# untitled.net
KiCad netlist of a schematic drawn in EAGLE
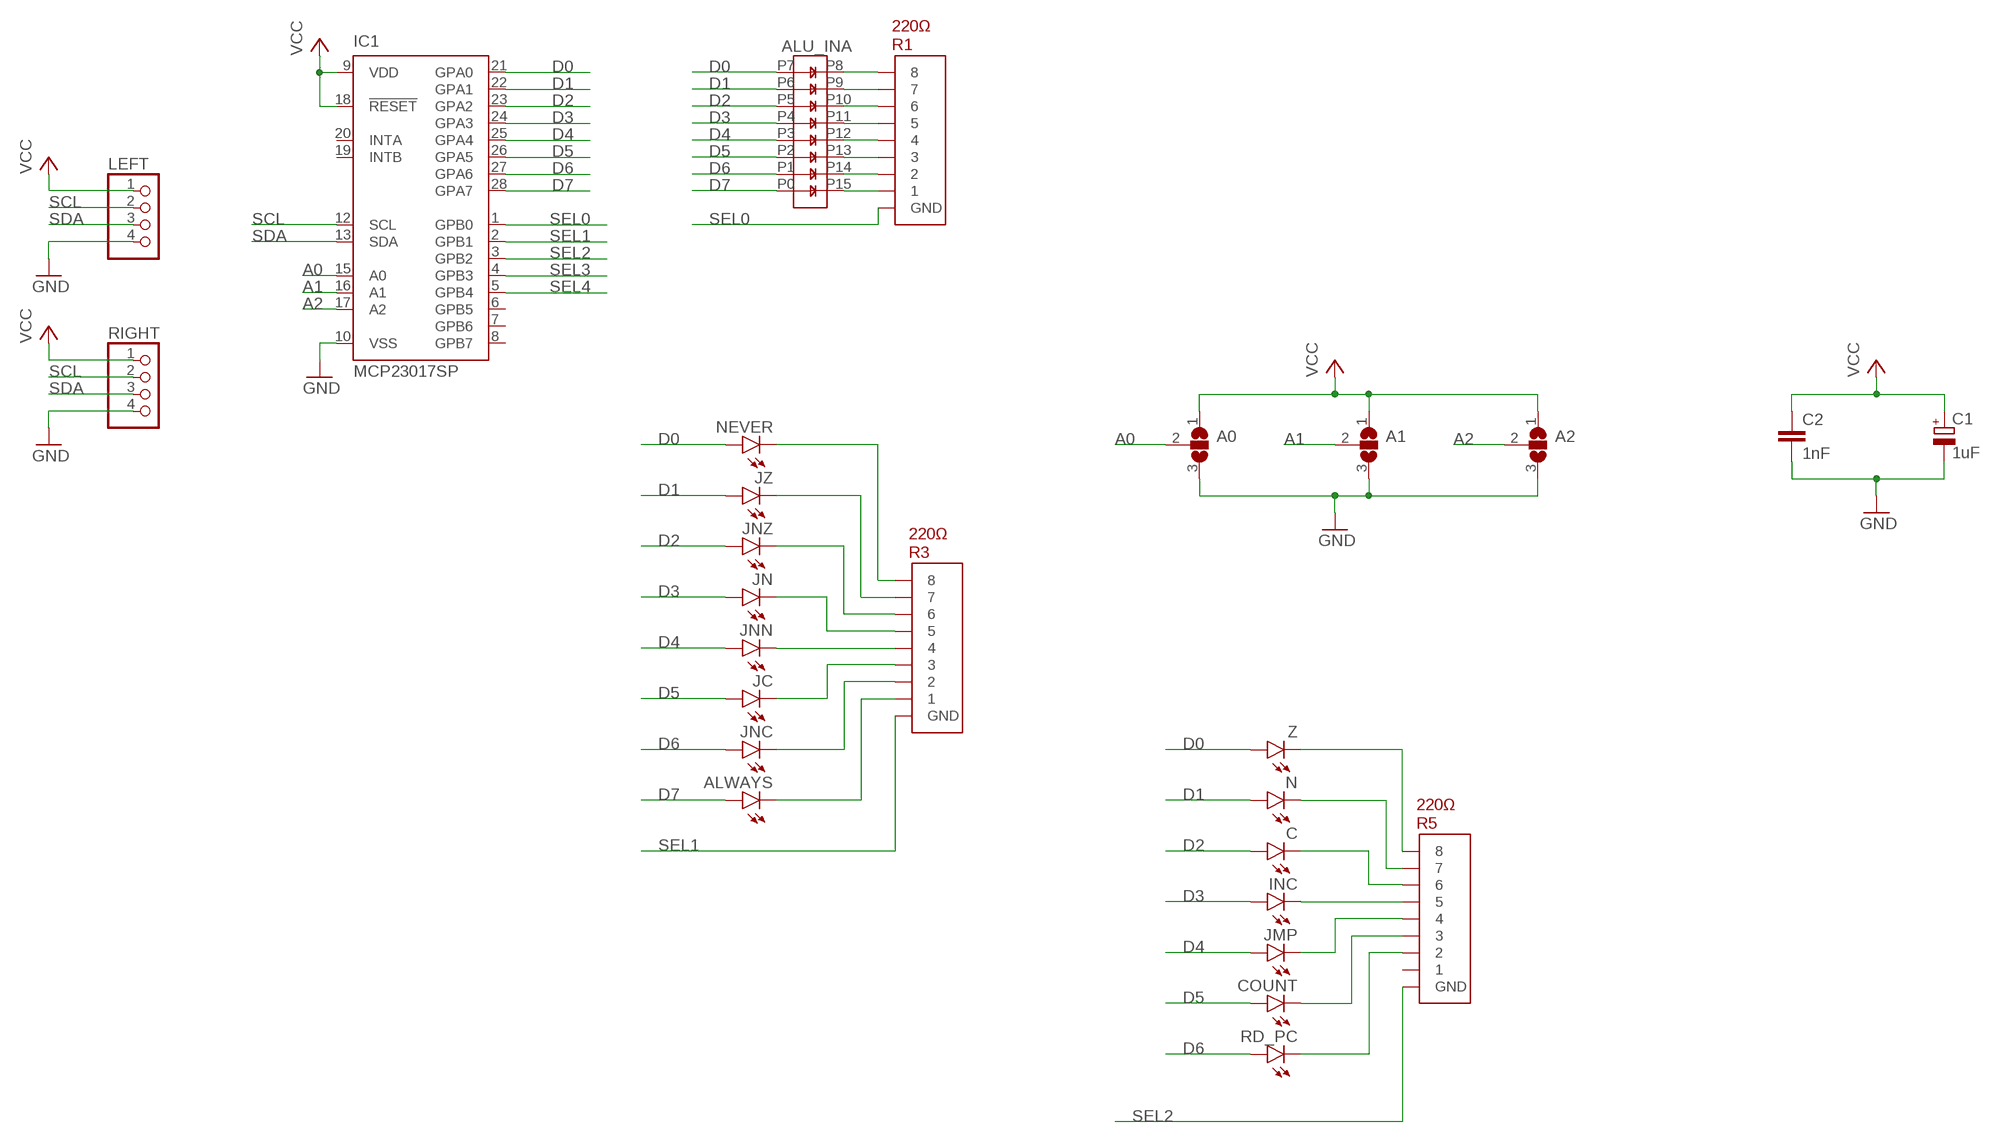
[diagram p0: schematic, sheet 1]

(export (version "E")
  (design (tool "Eeschema 10.0.6"))
  (components
    (comp (ref "A0")
      (value "SJ2W")
      (footprint "eagle-import:SJ_2")
      (libsource (lib "eagle-import") (part "SJ2W"))
    )
    (comp (ref "A1")
      (value "SJ2W")
      (footprint "eagle-import:SJ_2")
      (libsource (lib "eagle-import") (part "SJ2W"))
    )
    (comp (ref "A2")
      (value "SJ2W")
      (footprint "eagle-import:SJ_2")
      (libsource (lib "eagle-import") (part "SJ2W"))
    )
    (comp (ref "ALU_INA")
      (value "LB8")
      (footprint "eagle-import:LB8")
      (libsource (lib "eagle-import") (part "LB8"))
    )
    (comp (ref "ALWAYS")
      (value "LED3MM")
      (footprint "eagle-import:LED3MM")
      (libsource (lib "eagle-import") (part "LED3MM"))
    )
    (comp (ref "C")
      (value "LED3MM")
      (footprint "eagle-import:LED3MM")
      (libsource (lib "eagle-import") (part "LED3MM"))
    )
    (comp (ref "C1")
      (value "1uF")
      (footprint "eagle-import:E2,5-6")
      (libsource (lib "eagle-import") (part "CPOL-EUE2.5-6"))
    )
    (comp (ref "C2")
      (value "1nF")
      (footprint "eagle-import:C2.5-2")
      (libsource (lib "eagle-import") (part "C2.5/2"))
    )
    (comp (ref "COUNT")
      (value "LED3MM")
      (footprint "eagle-import:LED3MM")
      (libsource (lib "eagle-import") (part "LED3MM"))
    )
    (comp (ref "IC1")
      (value "MCP23017SP")
      (footprint "eagle-import:DIL28-3")
      (fields (field (name "MF") "MICROCHIP") (field (name "MPN") "MCP23017-E/SP"))
      (libsource (lib "eagle-import") (part "MCP23017SP"))
    )
    (comp (ref "INC")
      (value "LED3MM")
      (footprint "eagle-import:LED3MM")
      (libsource (lib "eagle-import") (part "LED3MM"))
    )
    (comp (ref "JC")
      (value "LED3MM")
      (footprint "eagle-import:LED3MM")
      (libsource (lib "eagle-import") (part "LED3MM"))
    )
    (comp (ref "JMP")
      (value "LED3MM")
      (footprint "eagle-import:LED3MM")
      (libsource (lib "eagle-import") (part "LED3MM"))
    )
    (comp (ref "JN")
      (value "LED3MM")
      (footprint "eagle-import:LED3MM")
      (libsource (lib "eagle-import") (part "LED3MM"))
    )
    (comp (ref "JNC")
      (value "LED3MM")
      (footprint "eagle-import:LED3MM")
      (libsource (lib "eagle-import") (part "LED3MM"))
    )
    (comp (ref "JNN")
      (value "LED3MM")
      (footprint "eagle-import:LED3MM")
      (libsource (lib "eagle-import") (part "LED3MM"))
    )
    (comp (ref "JNZ")
      (value "LED3MM")
      (footprint "eagle-import:LED3MM")
      (libsource (lib "eagle-import") (part "LED3MM"))
    )
    (comp (ref "JZ")
      (value "LED3MM")
      (footprint "eagle-import:LED3MM")
      (libsource (lib "eagle-import") (part "LED3MM"))
    )
    (comp (ref "LEFT")
      (value "PINHD-1X4")
      (footprint "eagle-import:1X04")
      (libsource (lib "eagle-import") (part "PINHD-1X4"))
    )
    (comp (ref "N")
      (value "LED3MM")
      (footprint "eagle-import:LED3MM")
      (libsource (lib "eagle-import") (part "LED3MM"))
    )
    (comp (ref "NEVER")
      (value "LED3MM")
      (footprint "eagle-import:LED3MM")
      (libsource (lib "eagle-import") (part "LED3MM"))
    )
    (comp (ref "R1")
      (value "220Ω")
      (footprint "eagle-import:R_ARRAY_8PIN")
      (libsource (lib "eagle-import") (part "R_ARRAY_8PIN"))
    )
    (comp (ref "R3")
      (value "220Ω")
      (footprint "eagle-import:R_ARRAY_8PIN")
      (libsource (lib "eagle-import") (part "R_ARRAY_8PIN"))
    )
    (comp (ref "R5")
      (value "220Ω")
      (footprint "eagle-import:R_ARRAY_8PIN")
      (libsource (lib "eagle-import") (part "R_ARRAY_8PIN"))
    )
    (comp (ref "RD_PC")
      (value "LED3MM")
      (footprint "eagle-import:LED3MM")
      (libsource (lib "eagle-import") (part "LED3MM"))
    )
    (comp (ref "RIGHT")
      (value "PINHD-1X4")
      (footprint "eagle-import:1X04")
      (libsource (lib "eagle-import") (part "PINHD-1X4"))
    )
    (comp (ref "Z")
      (value "LED3MM")
      (footprint "eagle-import:LED3MM")
      (libsource (lib "eagle-import") (part "LED3MM"))
    )
  )
  (nets
    (net (code "1") (name "/A0") (class "Default")
      (node (ref "A0") (pin "2") (pinfunction "2_2") (pintype "passive"))
      (node (ref "IC1") (pin "15") (pinfunction "A0_15") (pintype "input"))
    )
    (net (code "2") (name "/A1") (class "Default")
      (node (ref "A1") (pin "2") (pinfunction "2_2") (pintype "passive"))
      (node (ref "IC1") (pin "16") (pinfunction "A1_16") (pintype "input"))
    )
    (net (code "3") (name "/A2") (class "Default")
      (node (ref "A2") (pin "2") (pinfunction "2_2") (pintype "passive"))
      (node (ref "IC1") (pin "17") (pinfunction "A2_17") (pintype "input"))
    )
    (net (code "4") (name "/D0") (class "Default")
      (node (ref "ALU_INA") (pin "P7") (pinfunction "P7_P7") (pintype "bidirectional"))
      (node (ref "IC1") (pin "21") (pinfunction "GPA0_21") (pintype "bidirectional"))
      (node (ref "NEVER") (pin "A") (pinfunction "A_A") (pintype "passive"))
      (node (ref "Z") (pin "A") (pinfunction "A_A") (pintype "passive"))
    )
    (net (code "5") (name "/D1") (class "Default")
      (node (ref "ALU_INA") (pin "P6") (pinfunction "P6_P6") (pintype "bidirectional"))
      (node (ref "IC1") (pin "22") (pinfunction "GPA1_22") (pintype "bidirectional"))
      (node (ref "JZ") (pin "A") (pinfunction "A_A") (pintype "passive"))
      (node (ref "N") (pin "A") (pinfunction "A_A") (pintype "passive"))
    )
    (net (code "6") (name "/D2") (class "Default")
      (node (ref "ALU_INA") (pin "P5") (pinfunction "P5_P5") (pintype "bidirectional"))
      (node (ref "C") (pin "A") (pinfunction "A_A") (pintype "passive"))
      (node (ref "IC1") (pin "23") (pinfunction "GPA2_23") (pintype "bidirectional"))
      (node (ref "JNZ") (pin "A") (pinfunction "A_A") (pintype "passive"))
    )
    (net (code "7") (name "/D3") (class "Default")
      (node (ref "ALU_INA") (pin "P4") (pinfunction "P4_P4") (pintype "bidirectional"))
      (node (ref "IC1") (pin "24") (pinfunction "GPA3_24") (pintype "bidirectional"))
      (node (ref "INC") (pin "A") (pinfunction "A_A") (pintype "passive"))
      (node (ref "JN") (pin "A") (pinfunction "A_A") (pintype "passive"))
    )
    (net (code "8") (name "/D4") (class "Default")
      (node (ref "ALU_INA") (pin "P3") (pinfunction "P3_P3") (pintype "bidirectional"))
      (node (ref "IC1") (pin "25") (pinfunction "GPA4_25") (pintype "bidirectional"))
      (node (ref "JMP") (pin "A") (pinfunction "A_A") (pintype "passive"))
      (node (ref "JNN") (pin "A") (pinfunction "A_A") (pintype "passive"))
    )
    (net (code "9") (name "/D5") (class "Default")
      (node (ref "ALU_INA") (pin "P2") (pinfunction "P2_P2") (pintype "bidirectional"))
      (node (ref "COUNT") (pin "A") (pinfunction "A_A") (pintype "passive"))
      (node (ref "IC1") (pin "26") (pinfunction "GPA5_26") (pintype "bidirectional"))
      (node (ref "JC") (pin "A") (pinfunction "A_A") (pintype "passive"))
    )
    (net (code "10") (name "/D6") (class "Default")
      (node (ref "ALU_INA") (pin "P1") (pinfunction "P1_P1") (pintype "bidirectional"))
      (node (ref "IC1") (pin "27") (pinfunction "GPA6_27") (pintype "bidirectional"))
      (node (ref "JNC") (pin "A") (pinfunction "A_A") (pintype "passive"))
      (node (ref "RD_PC") (pin "A") (pinfunction "A_A") (pintype "passive"))
    )
    (net (code "11") (name "/D7") (class "Default")
      (node (ref "ALU_INA") (pin "P0") (pinfunction "P0_P0") (pintype "bidirectional"))
      (node (ref "ALWAYS") (pin "A") (pinfunction "A_A") (pintype "passive"))
      (node (ref "IC1") (pin "28") (pinfunction "GPA7_28") (pintype "bidirectional"))
    )
    (net (code "12") (name "/SCL") (class "Default")
      (node (ref "IC1") (pin "12") (pinfunction "SCL_12") (pintype "input"))
      (node (ref "LEFT") (pin "2") (pinfunction "2_2") (pintype "passive"))
      (node (ref "RIGHT") (pin "2") (pinfunction "2_2") (pintype "passive"))
    )
    (net (code "13") (name "/SDA") (class "Default")
      (node (ref "IC1") (pin "13") (pinfunction "SDA_13") (pintype "bidirectional"))
      (node (ref "LEFT") (pin "3") (pinfunction "3_3") (pintype "passive"))
      (node (ref "RIGHT") (pin "3") (pinfunction "3_3") (pintype "passive"))
    )
    (net (code "14") (name "/SEL0") (class "Default")
      (node (ref "IC1") (pin "1") (pinfunction "GPB0_1") (pintype "bidirectional"))
      (node (ref "R1") (pin "GND") (pinfunction "GND_GND") (pintype "bidirectional"))
    )
    (net (code "15") (name "/SEL1") (class "Default")
      (node (ref "IC1") (pin "2") (pinfunction "GPB1_2") (pintype "bidirectional"))
      (node (ref "R3") (pin "GND") (pinfunction "GND_GND") (pintype "bidirectional"))
    )
    (net (code "16") (name "/SEL2") (class "Default")
      (node (ref "IC1") (pin "3") (pinfunction "GPB2_3") (pintype "bidirectional"))
      (node (ref "R5") (pin "GND") (pinfunction "GND_GND") (pintype "bidirectional"))
    )
    (net (code "17") (name "/SEL3") (class "Default")
      (node (ref "IC1") (pin "4") (pinfunction "GPB3_4") (pintype "bidirectional"))
    )
    (net (code "18") (name "/SEL4") (class "Default")
      (node (ref "IC1") (pin "5") (pinfunction "GPB4_5") (pintype "bidirectional"))
    )
    (net (code "19") (name "GND") (class "Default")
      (node (ref "A0") (pin "3") (pinfunction "3_3") (pintype "passive"))
      (node (ref "A1") (pin "3") (pinfunction "3_3") (pintype "passive"))
      (node (ref "A2") (pin "3") (pinfunction "3_3") (pintype "passive"))
      (node (ref "C1") (pin "-") (pinfunction "-_-") (pintype "passive"))
      (node (ref "C2") (pin "2") (pinfunction "2_2") (pintype "passive"))
      (node (ref "IC1") (pin "10") (pinfunction "VSS_10") (pintype "power_in"))
      (node (ref "LEFT") (pin "4") (pinfunction "4_4") (pintype "passive"))
      (node (ref "RIGHT") (pin "4") (pinfunction "4_4") (pintype "passive"))
    )
    (net (code "20") (name "Net-(ALU_INA-PadP8)") (class "Default")
      (node (ref "ALU_INA") (pin "P8") (pinfunction "P8_P8") (pintype "bidirectional"))
      (node (ref "R1") (pin "8") (pinfunction "8_8") (pintype "bidirectional"))
    )
    (net (code "21") (name "Net-(ALU_INA-PadP9)") (class "Default")
      (node (ref "ALU_INA") (pin "P9") (pinfunction "P9_P9") (pintype "bidirectional"))
      (node (ref "R1") (pin "7") (pinfunction "7_7") (pintype "bidirectional"))
    )
    (net (code "22") (name "Net-(ALU_INA-PadP10)") (class "Default")
      (node (ref "ALU_INA") (pin "P10") (pinfunction "P10_P10") (pintype "bidirectional"))
      (node (ref "R1") (pin "6") (pinfunction "6_6") (pintype "bidirectional"))
    )
    (net (code "23") (name "Net-(ALU_INA-PadP11)") (class "Default")
      (node (ref "ALU_INA") (pin "P11") (pinfunction "P11_P11") (pintype "bidirectional"))
      (node (ref "R1") (pin "5") (pinfunction "5_5") (pintype "bidirectional"))
    )
    (net (code "24") (name "Net-(ALU_INA-PadP12)") (class "Default")
      (node (ref "ALU_INA") (pin "P12") (pinfunction "P12_P12") (pintype "bidirectional"))
      (node (ref "R1") (pin "4") (pinfunction "4_4") (pintype "bidirectional"))
    )
    (net (code "25") (name "Net-(ALU_INA-PadP13)") (class "Default")
      (node (ref "ALU_INA") (pin "P13") (pinfunction "P13_P13") (pintype "bidirectional"))
      (node (ref "R1") (pin "3") (pinfunction "3_3") (pintype "bidirectional"))
    )
    (net (code "26") (name "Net-(ALU_INA-PadP14)") (class "Default")
      (node (ref "ALU_INA") (pin "P14") (pinfunction "P14_P14") (pintype "bidirectional"))
      (node (ref "R1") (pin "2") (pinfunction "2_2") (pintype "bidirectional"))
    )
    (net (code "27") (name "Net-(ALU_INA-PadP15)") (class "Default")
      (node (ref "ALU_INA") (pin "P15") (pinfunction "P15_P15") (pintype "bidirectional"))
      (node (ref "R1") (pin "1") (pinfunction "1_1") (pintype "bidirectional"))
    )
    (net (code "28") (name "Net-(ALWAYS-C)") (class "Default")
      (node (ref "ALWAYS") (pin "K") (pinfunction "C_K") (pintype "passive"))
      (node (ref "R3") (pin "1") (pinfunction "1_1") (pintype "bidirectional"))
    )
    (net (code "29") (name "Net-(C-C)") (class "Default")
      (node (ref "C") (pin "K") (pinfunction "C_K") (pintype "passive"))
      (node (ref "R5") (pin "6") (pinfunction "6_6") (pintype "bidirectional"))
    )
    (net (code "30") (name "Net-(COUNT-C)") (class "Default")
      (node (ref "COUNT") (pin "K") (pinfunction "C_K") (pintype "passive"))
      (node (ref "R5") (pin "3") (pinfunction "3_3") (pintype "bidirectional"))
    )
    (net (code "31") (name "Net-(INC-C)") (class "Default")
      (node (ref "INC") (pin "K") (pinfunction "C_K") (pintype "passive"))
      (node (ref "R5") (pin "5") (pinfunction "5_5") (pintype "bidirectional"))
    )
    (net (code "32") (name "Net-(JC-C)") (class "Default")
      (node (ref "JC") (pin "K") (pinfunction "C_K") (pintype "passive"))
      (node (ref "R3") (pin "3") (pinfunction "3_3") (pintype "bidirectional"))
    )
    (net (code "33") (name "Net-(JMP-C)") (class "Default")
      (node (ref "JMP") (pin "K") (pinfunction "C_K") (pintype "passive"))
      (node (ref "R5") (pin "4") (pinfunction "4_4") (pintype "bidirectional"))
    )
    (net (code "34") (name "Net-(JN-C)") (class "Default")
      (node (ref "JN") (pin "K") (pinfunction "C_K") (pintype "passive"))
      (node (ref "R3") (pin "5") (pinfunction "5_5") (pintype "bidirectional"))
    )
    (net (code "35") (name "Net-(JNC-C)") (class "Default")
      (node (ref "JNC") (pin "K") (pinfunction "C_K") (pintype "passive"))
      (node (ref "R3") (pin "2") (pinfunction "2_2") (pintype "bidirectional"))
    )
    (net (code "36") (name "Net-(JNN-C)") (class "Default")
      (node (ref "JNN") (pin "K") (pinfunction "C_K") (pintype "passive"))
      (node (ref "R3") (pin "4") (pinfunction "4_4") (pintype "bidirectional"))
    )
    (net (code "37") (name "Net-(JNZ-C)") (class "Default")
      (node (ref "JNZ") (pin "K") (pinfunction "C_K") (pintype "passive"))
      (node (ref "R3") (pin "6") (pinfunction "6_6") (pintype "bidirectional"))
    )
    (net (code "38") (name "Net-(JZ-C)") (class "Default")
      (node (ref "JZ") (pin "K") (pinfunction "C_K") (pintype "passive"))
      (node (ref "R3") (pin "7") (pinfunction "7_7") (pintype "bidirectional"))
    )
    (net (code "39") (name "Net-(N-C)") (class "Default")
      (node (ref "N") (pin "K") (pinfunction "C_K") (pintype "passive"))
      (node (ref "R5") (pin "7") (pinfunction "7_7") (pintype "bidirectional"))
    )
    (net (code "40") (name "Net-(NEVER-C)") (class "Default")
      (node (ref "NEVER") (pin "K") (pinfunction "C_K") (pintype "passive"))
      (node (ref "R3") (pin "8") (pinfunction "8_8") (pintype "bidirectional"))
    )
    (net (code "41") (name "Net-(RD_PC-C)") (class "Default")
      (node (ref "R5") (pin "2") (pinfunction "2_2") (pintype "bidirectional"))
      (node (ref "RD_PC") (pin "K") (pinfunction "C_K") (pintype "passive"))
    )
    (net (code "42") (name "Net-(Z-C)") (class "Default")
      (node (ref "R5") (pin "8") (pinfunction "8_8") (pintype "bidirectional"))
      (node (ref "Z") (pin "K") (pinfunction "C_K") (pintype "passive"))
    )
    (net (code "43") (name "VCC") (class "Default")
      (node (ref "A0") (pin "1") (pinfunction "1_1") (pintype "passive"))
      (node (ref "A1") (pin "1") (pinfunction "1_1") (pintype "passive"))
      (node (ref "A2") (pin "1") (pinfunction "1_1") (pintype "passive"))
      (node (ref "C1") (pin "+") (pinfunction "+_+") (pintype "passive"))
      (node (ref "C2") (pin "1") (pinfunction "1_1") (pintype "passive"))
      (node (ref "IC1") (pin "18") (pinfunction "~{RESET}_18") (pintype "input"))
      (node (ref "IC1") (pin "9") (pinfunction "VDD_9") (pintype "power_in"))
      (node (ref "LEFT") (pin "1") (pinfunction "1_1") (pintype "passive"))
      (node (ref "RIGHT") (pin "1") (pinfunction "1_1") (pintype "passive"))
    )
    (net (code "44") (name "unconnected-(IC1-GPB5-Pad6)") (class "Default")
      (node (ref "IC1") (pin "6") (pinfunction "GPB5_6") (pintype "bidirectional"))
    )
    (net (code "45") (name "unconnected-(IC1-GPB6-Pad7)") (class "Default")
      (node (ref "IC1") (pin "7") (pinfunction "GPB6_7") (pintype "bidirectional"))
    )
    (net (code "46") (name "unconnected-(IC1-GPB7-Pad8)") (class "Default")
      (node (ref "IC1") (pin "8") (pinfunction "GPB7_8") (pintype "bidirectional"))
    )
    (net (code "47") (name "unconnected-(IC1-INTA-Pad20)") (class "Default")
      (node (ref "IC1") (pin "20") (pinfunction "INTA_20") (pintype "output"))
    )
    (net (code "48") (name "unconnected-(IC1-INTB-Pad19)") (class "Default")
      (node (ref "IC1") (pin "19") (pinfunction "INTB_19") (pintype "output"))
    )
    (net (code "49") (name "unconnected-(R5-Pad1)") (class "Default")
      (node (ref "R5") (pin "1") (pinfunction "1_1") (pintype "bidirectional"))
    )
  )
)
